# LED.net
KiCad netlist of a schematic drawn in Altium Designer
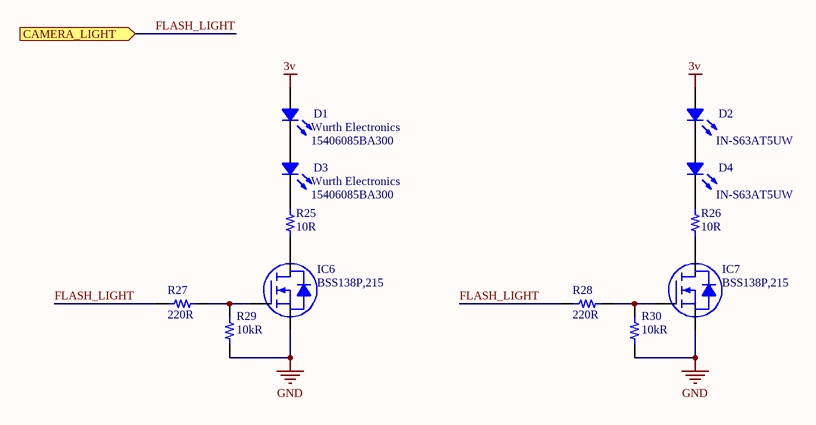
[diagram p0: LED.SchDoc]

(export (version "E")
  (design (tool "Eeschema 10.0.6"))
  (components
    (comp (ref "D1")
      (value "15406085BA300")
      (footprint "LED 0603/1608")
      (description "Chip LED")
      (fields (field (name "MANUFACTURER") "Wurth Electronics"))
      (libsource (lib "yildizIoT Library") (part "LED"))
    )
    (comp (ref "D2")
      (value "IN-S63AT5UW")
      (footprint "LED 0603/1608")
      (description "Chip LED")
      (fields (field (name "MANUFACTURER") "Inolux"))
      (libsource (lib "yildizIoT Library") (part "LED"))
    )
    (comp (ref "D3")
      (value "15406085BA300")
      (footprint "LED 0603/1608")
      (description "Chip LED")
      (fields (field (name "MANUFACTURER") "Wurth Electronics"))
      (libsource (lib "yildizIoT Library") (part "LED"))
    )
    (comp (ref "D4")
      (value "IN-S63AT5UW")
      (footprint "LED 0603/1608")
      (description "Chip LED")
      (fields (field (name "MANUFACTURER") "Inolux"))
      (libsource (lib "yildizIoT Library") (part "LED"))
    )
    (comp (ref "IC6")
      (value "BSS138P,215")
      (footprint "DIODES SOT-23-3")
      (description "MOSFET N-CH 50V 200MA SOT23-3")
      (fields (field (name "MANUFACTURER") "Nexperia"))
      (libsource (lib "Celestial Altium Library - altium_library") (part "DIODES INC MOSFET N-CH SOT-23-3"))
    )
    (comp (ref "IC7")
      (value "BSS138P,215")
      (footprint "DIODES SOT-23-3")
      (description "MOSFET N-CH 50V 200MA SOT23-3")
      (fields (field (name "MANUFACTURER") "Nexperia"))
      (libsource (lib "Celestial Altium Library - altium_library") (part "DIODES INC MOSFET N-CH SOT-23-3"))
    )
    (comp (ref "R25")
      (value "10R")
      (footprint "RES 0603/1608")
      (description "Ceramic, SMT Capacitor")
      (fields
        (field (name "MANUFACTURER") "Yageo")
        (field (name "MANUFACTURER PART NUMBER") "RC0603FR-0710RL")
      )
      (libsource (lib "yildizIoT Library") (part "Resistor_Chip"))
    )
    (comp (ref "R26")
      (value "10R")
      (footprint "RES 0603/1608")
      (description "Ceramic, SMT Capacitor")
      (fields
        (field (name "MANUFACTURER") "Yageo")
        (field (name "MANUFACTURER PART NUMBER") "RC0603FR-0710RL")
      )
      (libsource (lib "yildizIoT Library") (part "Resistor_Chip"))
    )
    (comp (ref "R27")
      (value "220R")
      (footprint "RES 0603/1608")
      (description "Ceramic, SMT Capacitor")
      (fields
        (field (name "MANUFACTURER") "Yageo")
        (field (name "MANUFACTURER PART NUMBER") "RC0603FR-07220RL")
      )
      (libsource (lib "yildizIoT Library") (part "Resistor_Chip"))
    )
    (comp (ref "R28")
      (value "220R")
      (footprint "RES 0603/1608")
      (description "Ceramic, SMT Capacitor")
      (fields
        (field (name "MANUFACTURER") "Yageo")
        (field (name "MANUFACTURER PART NUMBER") "RC0603FR-07220RL")
      )
      (libsource (lib "yildizIoT Library") (part "Resistor_Chip"))
    )
    (comp (ref "R29")
      (value "10kR")
      (footprint "RES 0603/1608")
      (description "Ceramic, SMT Capacitor")
      (fields
        (field (name "MANUFACTURER") "Stackpole Electronics")
        (field (name "MANUFACTURER PART NUMBER") "RNCP0603FTD10K0")
      )
      (libsource (lib "yildizIoT Library") (part "Resistor_Chip"))
    )
    (comp (ref "R30")
      (value "10kR")
      (footprint "RES 0603/1608")
      (description "Ceramic, SMT Capacitor")
      (fields
        (field (name "MANUFACTURER") "Stackpole Electronics")
        (field (name "MANUFACTURER PART NUMBER") "RNCP0603FTD10K0")
      )
      (libsource (lib "yildizIoT Library") (part "Resistor_Chip"))
    )
  )
  (nets
    (net (code "1") (name "/FLASH_LIGHT") (class "Default")
      (node (ref "R27") (pin "1") (pinfunction "1_1") (pintype "passive"))
      (node (ref "R28") (pin "1") (pinfunction "1_1") (pintype "passive"))
    )
    (net (code "2") (name "3v") (class "Default")
      (node (ref "D1") (pin "1") (pinfunction "1_1") (pintype "passive"))
      (node (ref "D2") (pin "1") (pinfunction "1_1") (pintype "passive"))
    )
    (net (code "3") (name "GND") (class "Default")
      (node (ref "IC6") (pin "2") (pinfunction "S_2") (pintype "passive"))
      (node (ref "IC7") (pin "2") (pinfunction "S_2") (pintype "passive"))
      (node (ref "R29") (pin "2") (pinfunction "2_2") (pintype "passive"))
      (node (ref "R30") (pin "2") (pinfunction "2_2") (pintype "passive"))
    )
    (net (code "4") (name "Net-(D1-Pad2)") (class "Default")
      (node (ref "D1") (pin "2") (pinfunction "2_2") (pintype "passive"))
      (node (ref "D3") (pin "1") (pinfunction "1_1") (pintype "passive"))
    )
    (net (code "5") (name "Net-(D2-Pad2)") (class "Default")
      (node (ref "D2") (pin "2") (pinfunction "2_2") (pintype "passive"))
      (node (ref "D4") (pin "1") (pinfunction "1_1") (pintype "passive"))
    )
    (net (code "6") (name "Net-(D3-Pad2)") (class "Default")
      (node (ref "D3") (pin "2") (pinfunction "2_2") (pintype "passive"))
      (node (ref "R25") (pin "2") (pinfunction "2_2") (pintype "passive"))
    )
    (net (code "7") (name "Net-(D4-Pad2)") (class "Default")
      (node (ref "D4") (pin "2") (pinfunction "2_2") (pintype "passive"))
      (node (ref "R26") (pin "2") (pinfunction "2_2") (pintype "passive"))
    )
    (net (code "8") (name "Net-(IC6-D)") (class "Default")
      (node (ref "IC6") (pin "3") (pinfunction "D_3") (pintype "passive"))
      (node (ref "R25") (pin "1") (pinfunction "1_1") (pintype "passive"))
    )
    (net (code "9") (name "Net-(IC6-G)") (class "Default")
      (node (ref "IC6") (pin "1") (pinfunction "G_1") (pintype "passive"))
      (node (ref "R27") (pin "2") (pinfunction "2_2") (pintype "passive"))
      (node (ref "R29") (pin "1") (pinfunction "1_1") (pintype "passive"))
    )
    (net (code "10") (name "Net-(IC7-D)") (class "Default")
      (node (ref "IC7") (pin "3") (pinfunction "D_3") (pintype "passive"))
      (node (ref "R26") (pin "1") (pinfunction "1_1") (pintype "passive"))
    )
    (net (code "11") (name "Net-(IC7-G)") (class "Default")
      (node (ref "IC7") (pin "1") (pinfunction "G_1") (pintype "passive"))
      (node (ref "R28") (pin "2") (pinfunction "2_2") (pintype "passive"))
      (node (ref "R30") (pin "1") (pinfunction "1_1") (pintype "passive"))
    )
  )
)
